# Final.net
KiCad netlist of a schematic drawn in EAGLE
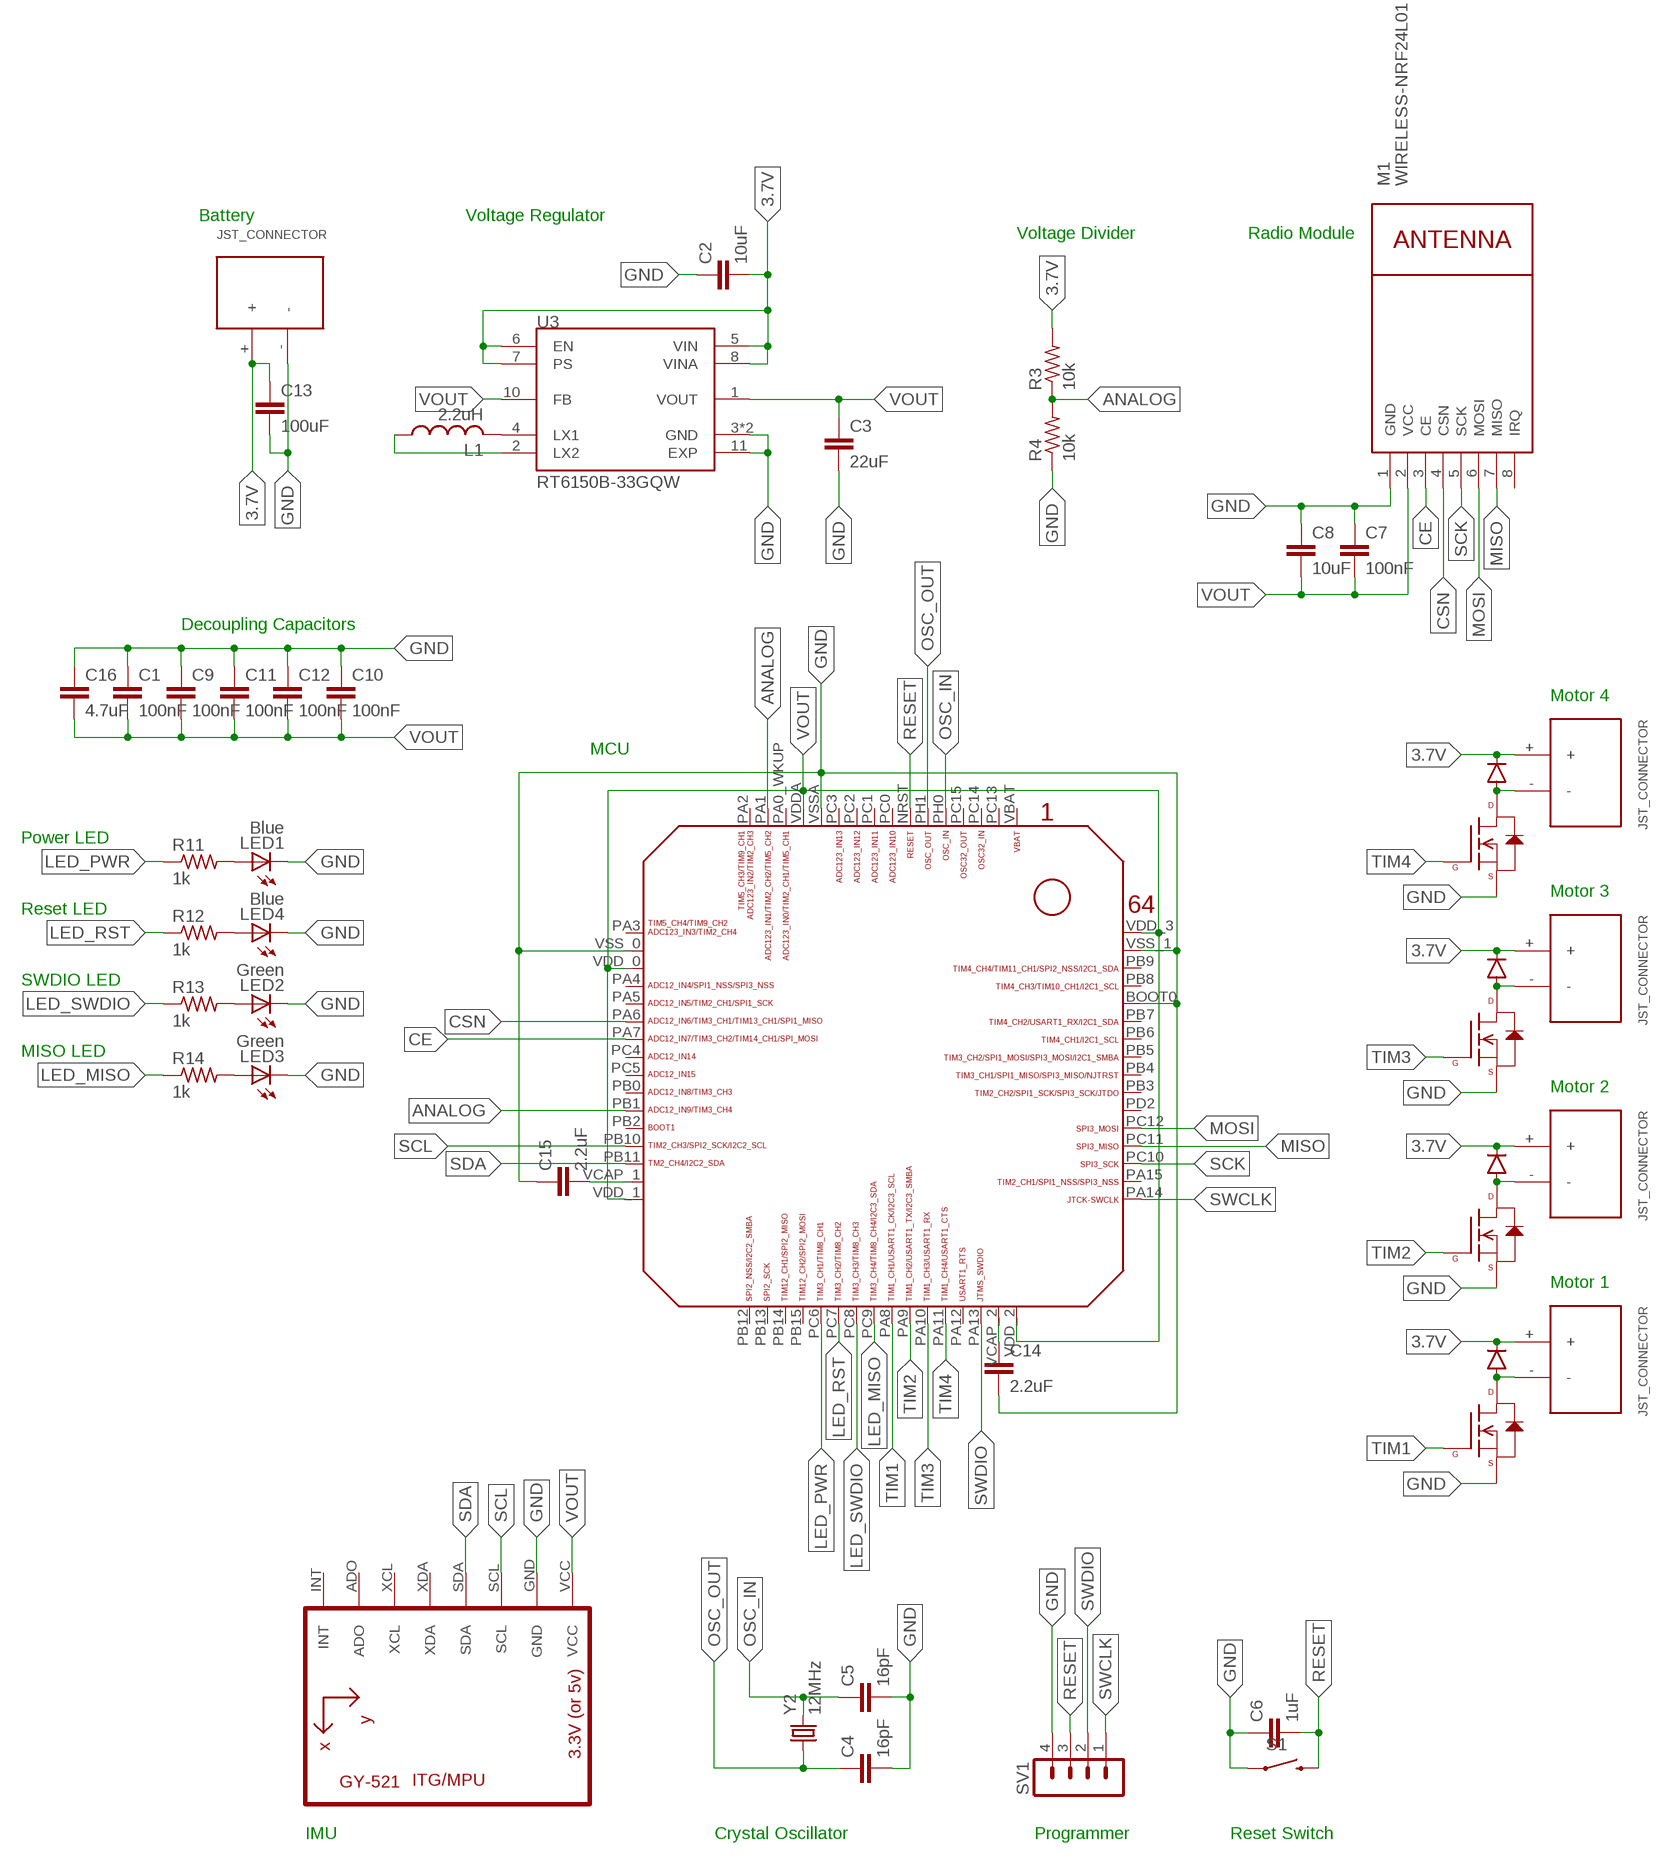
[diagram p0: schematic, sheet 1]

(export (version "E")
  (design (tool "Eeschema 10.0.6"))
  (components
    (comp (ref "C1")
      (value "100nF")
      (footprint "eagle-import:C0603")
      (libsource (lib "eagle-import") (part "rcl_334_C-EUC0603"))
    )
    (comp (ref "C2")
      (value "10uF")
      (footprint "eagle-import:C0603")
      (libsource (lib "eagle-import") (part "rcl_334_C-EUC0603"))
    )
    (comp (ref "C3")
      (value "22uF")
      (footprint "eagle-import:C0603")
      (libsource (lib "eagle-import") (part "rcl_334_C-EUC0603"))
    )
    (comp (ref "C4")
      (value "16pF")
      (footprint "eagle-import:C0603")
      (libsource (lib "eagle-import") (part "rcl_334_C-EUC0603"))
    )
    (comp (ref "C5")
      (value "16pF")
      (footprint "eagle-import:C0603")
      (libsource (lib "eagle-import") (part "rcl_334_C-EUC0603"))
    )
    (comp (ref "C6")
      (value "1uF")
      (footprint "eagle-import:C0603")
      (libsource (lib "eagle-import") (part "rcl_334_C-EUC0603"))
    )
    (comp (ref "C7")
      (value "100nF")
      (footprint "eagle-import:C0603")
      (libsource (lib "eagle-import") (part "rcl_334_C-EUC0603"))
    )
    (comp (ref "C8")
      (value "10uF")
      (footprint "eagle-import:C0603")
      (libsource (lib "eagle-import") (part "rcl_334_C-EUC0603"))
    )
    (comp (ref "C9")
      (value "100nF")
      (footprint "eagle-import:C0603")
      (libsource (lib "eagle-import") (part "rcl_334_C-EUC0603"))
    )
    (comp (ref "C10")
      (value "100nF")
      (footprint "eagle-import:C0603")
      (libsource (lib "eagle-import") (part "rcl_334_C-EUC0603"))
    )
    (comp (ref "C11")
      (value "100nF")
      (footprint "eagle-import:C0603")
      (libsource (lib "eagle-import") (part "rcl_334_C-EUC0603"))
    )
    (comp (ref "C12")
      (value "100nF")
      (footprint "eagle-import:C0603")
      (libsource (lib "eagle-import") (part "rcl_334_C-EUC0603"))
    )
    (comp (ref "C13")
      (value "100uF")
      (footprint "eagle-import:C1206")
      (libsource (lib "eagle-import") (part "rcl_334_C-EUC1206"))
    )
    (comp (ref "C14")
      (value "2.2uF")
      (footprint "eagle-import:C0603")
      (libsource (lib "eagle-import") (part "C-EUC0603"))
    )
    (comp (ref "C15")
      (value "2.2uF")
      (footprint "eagle-import:C0603")
      (libsource (lib "eagle-import") (part "C-EUC0603"))
    )
    (comp (ref "C16")
      (value "4.7uF")
      (footprint "eagle-import:C0603")
      (libsource (lib "eagle-import") (part "rcl_334_C-EUC0603"))
    )
    (comp (ref "L1")
      (value "2.2uH")
      (footprint "eagle-import:L0603")
      (libsource (lib "eagle-import") (part "L-USL0603"))
    )
    (comp (ref "LED1")
      (value "Blue")
      (footprint "eagle-import:CHIP-LED0603")
      (libsource (lib "eagle-import") (part "LEDCHIP-LED0603"))
    )
    (comp (ref "LED2")
      (value "Green")
      (footprint "eagle-import:CHIP-LED0603")
      (libsource (lib "eagle-import") (part "LEDCHIP-LED0603"))
    )
    (comp (ref "LED3")
      (value "Green")
      (footprint "eagle-import:CHIP-LED0603")
      (libsource (lib "eagle-import") (part "LEDCHIP-LED0603"))
    )
    (comp (ref "LED4")
      (value "Blue")
      (footprint "eagle-import:CHIP-LED0603")
      (libsource (lib "eagle-import") (part "LEDCHIP-LED0603"))
    )
    (comp (ref "M1")
      (value "WIRELESS-NRF24L01")
      (footprint "eagle-import:WIRELESS-NRF24L01")
      (libsource (lib "eagle-import") (part "WIRELESS-NRF24L01"))
    )
    (comp (ref "R3")
      (value "10k")
      (footprint "eagle-import:R0603")
      (libsource (lib "eagle-import") (part "R-US_R0603"))
    )
    (comp (ref "R4")
      (value "10k")
      (footprint "eagle-import:R0603")
      (libsource (lib "eagle-import") (part "R-US_R0603"))
    )
    (comp (ref "R11")
      (value "1k")
      (footprint "eagle-import:R0603")
      (libsource (lib "eagle-import") (part "R-US_R0603"))
    )
    (comp (ref "R12")
      (value "1k")
      (footprint "eagle-import:R0603")
      (libsource (lib "eagle-import") (part "R-US_R0603"))
    )
    (comp (ref "R13")
      (value "1k")
      (footprint "eagle-import:R0603")
      (libsource (lib "eagle-import") (part "R-US_R0603"))
    )
    (comp (ref "R14")
      (value "1k")
      (footprint "eagle-import:R0603")
      (libsource (lib "eagle-import") (part "R-US_R0603"))
    )
    (comp (ref "S1")
      (value "SWITCH-MOMENTARY-2SMD")
      (footprint "eagle-import:TACTILE-SWITCH-SMD")
      (libsource (lib "eagle-import") (part "SWITCH-MOMENTARY-2SMD"))
    )
    (comp (ref "SV1")
      (value "MA04-1")
      (footprint "eagle-import:MA04-1")
      (libsource (lib "eagle-import") (part "MA04-1"))
    )
    (comp (ref "U$1")
      (value "STM32F405/415_LQFP64")
      (footprint "eagle-import:STM32F405_415_LQFP64")
      (libsource (lib "eagle-import") (part "STM32F405/415_LQFP64"))
    )
    (comp (ref "U$2")
      (value "JST_CONNECTOR_FEMALE")
      (footprint "eagle-import:JST_CONNECTOR_FEMALE")
      (libsource (lib "eagle-import") (part "JST_CONNECTOR_FEMALE"))
    )
    (comp (ref "U$3")
      (value "JST_CONNECTOR_FEMALE")
      (footprint "eagle-import:JST_CONNECTOR_FEMALE")
      (libsource (lib "eagle-import") (part "JST_CONNECTOR_FEMALE"))
    )
    (comp (ref "U$4")
      (value "JST_CONNECTOR_FEMALE")
      (footprint "eagle-import:JST_CONNECTOR_FEMALE")
      (libsource (lib "eagle-import") (part "JST_CONNECTOR_FEMALE"))
    )
    (comp (ref "U$5")
      (value "JST_CONNECTOR_FEMALE")
      (footprint "eagle-import:JST_CONNECTOR_FEMALE")
      (libsource (lib "eagle-import") (part "JST_CONNECTOR_FEMALE"))
    )
    (comp (ref "U$6")
      (value "JST_CONNECTOR_FEMALE")
      (footprint "eagle-import:JST_CONNECTOR_FEMALE")
      (libsource (lib "eagle-import") (part "JST_CONNECTOR_FEMALE"))
    )
    (comp (ref "U$7")
      (value "N-CHANNEL-MOSFET-IRLML6244TRPBF")
      (footprint "eagle-import:SOT23-3")
      (libsource (lib "eagle-import") (part "N-CHANNEL-MOSFET-IRLML6244TRPBF"))
    )
    (comp (ref "U$8")
      (value "N-CHANNEL-MOSFET-IRLML6244TRPBF")
      (footprint "eagle-import:SOT23-3")
      (libsource (lib "eagle-import") (part "N-CHANNEL-MOSFET-IRLML6244TRPBF"))
    )
    (comp (ref "U$9")
      (value "N-CHANNEL-MOSFET-IRLML6244TRPBF")
      (footprint "eagle-import:SOT23-3")
      (libsource (lib "eagle-import") (part "N-CHANNEL-MOSFET-IRLML6244TRPBF"))
    )
    (comp (ref "U$10")
      (value "N-CHANNEL-MOSFET-IRLML6244TRPBF")
      (footprint "eagle-import:SOT23-3")
      (libsource (lib "eagle-import") (part "N-CHANNEL-MOSFET-IRLML6244TRPBF"))
    )
    (comp (ref "U$11")
      (value "DB2W40300L")
      (footprint "eagle-import:MINI2-F3-B")
      (libsource (lib "eagle-import") (part "DB2W40300L"))
    )
    (comp (ref "U$12")
      (value "DB2W40300L")
      (footprint "eagle-import:MINI2-F3-B")
      (libsource (lib "eagle-import") (part "DB2W40300L"))
    )
    (comp (ref "U$13")
      (value "DB2W40300L")
      (footprint "eagle-import:MINI2-F3-B")
      (libsource (lib "eagle-import") (part "DB2W40300L"))
    )
    (comp (ref "U$14")
      (value "DB2W40300L")
      (footprint "eagle-import:MINI2-F3-B")
      (libsource (lib "eagle-import") (part "DB2W40300L"))
    )
    (comp (ref "U2")
      (value "GY-521MPU6050")
      (footprint "eagle-import:GY-521")
      (libsource (lib "eagle-import") (part "GY-521MPU6050"))
    )
    (comp (ref "U3")
      (value "RT6150B-33GQW")
      (footprint "eagle-import:SON50P250X250X80-11N")
      (fields (field (name "DIGI-KEY_PART_NUMBER") "RT6150B-33GQWCT-ND") (field (name "MF") "Richtek USA"))
      (libsource (lib "eagle-import") (part "RT6150B-33GQW"))
    )
    (comp (ref "Y2")
      (value "12MHz")
      (footprint "eagle-import:HC49UP")
      (libsource (lib "eagle-import") (part "CRYSTALSMD"))
    )
  )
  (nets
    (net (code "1") (name "3.7V") (class "Default")
      (node (ref "C13") (pin "1") (pinfunction "1_1") (pintype "passive"))
      (node (ref "C2") (pin "2") (pinfunction "2_2") (pintype "passive"))
      (node (ref "R3") (pin "2") (pinfunction "2_2") (pintype "passive"))
      (node (ref "U$11") (pin "NEG") (pinfunction "GPIN_NEG") (pintype "passive"))
      (node (ref "U$12") (pin "NEG") (pinfunction "GPIN_NEG") (pintype "passive"))
      (node (ref "U$13") (pin "NEG") (pinfunction "GPIN_NEG") (pintype "passive"))
      (node (ref "U$14") (pin "NEG") (pinfunction "GPIN_NEG") (pintype "passive"))
      (node (ref "U$2") (pin "+") (pinfunction "+_+") (pintype "bidirectional"))
      (node (ref "U$3") (pin "+") (pinfunction "+_+") (pintype "bidirectional"))
      (node (ref "U$4") (pin "+") (pinfunction "+_+") (pintype "bidirectional"))
      (node (ref "U$5") (pin "+") (pinfunction "+_+") (pintype "bidirectional"))
      (node (ref "U$6") (pin "+") (pinfunction "+_+") (pintype "bidirectional"))
      (node (ref "U3") (pin "5") (pinfunction "VIN_5") (pintype "power_in"))
      (node (ref "U3") (pin "6") (pinfunction "EN_6") (pintype "input"))
      (node (ref "U3") (pin "7") (pinfunction "PS_7") (pintype "input"))
      (node (ref "U3") (pin "8") (pinfunction "VINA_8") (pintype "power_in"))
    )
    (net (code "2") (name "ANALOG") (class "Default")
      (node (ref "R3") (pin "1") (pinfunction "1_1") (pintype "passive"))
      (node (ref "R4") (pin "2") (pinfunction "2_2") (pintype "passive"))
      (node (ref "U$1") (pin "PA1") (pinfunction "PA1_PA1") (pintype "bidirectional"))
      (node (ref "U$1") (pin "PB1") (pinfunction "PB1_PB1") (pintype "bidirectional"))
    )
    (net (code "3") (name "CE") (class "Default")
      (node (ref "M1") (pin "3") (pinfunction "CE_3") (pintype "bidirectional"))
      (node (ref "U$1") (pin "PA7") (pinfunction "PA7_PA7") (pintype "bidirectional"))
    )
    (net (code "4") (name "CSN") (class "Default")
      (node (ref "M1") (pin "4") (pinfunction "CSN_4") (pintype "bidirectional"))
      (node (ref "U$1") (pin "PA6") (pinfunction "PA6_PA6") (pintype "bidirectional"))
    )
    (net (code "5") (name "GND") (class "Default")
      (node (ref "C1") (pin "1") (pinfunction "1_1") (pintype "passive"))
      (node (ref "C10") (pin "1") (pinfunction "1_1") (pintype "passive"))
      (node (ref "C11") (pin "1") (pinfunction "1_1") (pintype "passive"))
      (node (ref "C12") (pin "1") (pinfunction "1_1") (pintype "passive"))
      (node (ref "C13") (pin "2") (pinfunction "2_2") (pintype "passive"))
      (node (ref "C14") (pin "2") (pinfunction "2_2") (pintype "passive"))
      (node (ref "C15") (pin "1") (pinfunction "1_1") (pintype "passive"))
      (node (ref "C16") (pin "1") (pinfunction "1_1") (pintype "passive"))
      (node (ref "C2") (pin "1") (pinfunction "1_1") (pintype "passive"))
      (node (ref "C3") (pin "2") (pinfunction "2_2") (pintype "passive"))
      (node (ref "C4") (pin "2") (pinfunction "2_2") (pintype "passive"))
      (node (ref "C5") (pin "2") (pinfunction "2_2") (pintype "passive"))
      (node (ref "C6") (pin "1") (pinfunction "1_1") (pintype "passive"))
      (node (ref "C7") (pin "1") (pinfunction "1_1") (pintype "passive"))
      (node (ref "C8") (pin "1") (pinfunction "1_1") (pintype "passive"))
      (node (ref "C9") (pin "1") (pinfunction "1_1") (pintype "passive"))
      (node (ref "LED1") (pin "C") (pinfunction "C_C") (pintype "passive"))
      (node (ref "LED2") (pin "C") (pinfunction "C_C") (pintype "passive"))
      (node (ref "LED3") (pin "C") (pinfunction "C_C") (pintype "passive"))
      (node (ref "LED4") (pin "C") (pinfunction "C_C") (pintype "passive"))
      (node (ref "M1") (pin "1") (pinfunction "GND_1") (pintype "power_in"))
      (node (ref "R4") (pin "1") (pinfunction "1_1") (pintype "passive"))
      (node (ref "S1") (pin "1") (pinfunction "1_1") (pintype "passive"))
      (node (ref "SV1") (pin "4") (pinfunction "4_4") (pintype "passive"))
      (node (ref "U$1") (pin "BOOT0") (pinfunction "BOOT0_BOOT0") (pintype "bidirectional"))
      (node (ref "U$1") (pin "VSSA") (pinfunction "VSSA_VSSA") (pintype "bidirectional"))
      (node (ref "U$1") (pin "VSS_0") (pinfunction "VSS_0_VSS_0") (pintype "bidirectional"))
      (node (ref "U$1") (pin "VSS_1") (pinfunction "VSS_1_VSS_1") (pintype "bidirectional"))
      (node (ref "U$10") (pin "2") (pinfunction "S_2") (pintype "passive"))
      (node (ref "U$2") (pin "-") (pinfunction "-_-") (pintype "bidirectional"))
      (node (ref "U$7") (pin "2") (pinfunction "S_2") (pintype "passive"))
      (node (ref "U$8") (pin "2") (pinfunction "S_2") (pintype "passive"))
      (node (ref "U$9") (pin "2") (pinfunction "S_2") (pintype "passive"))
      (node (ref "U2") (pin "GND") (pinfunction "GND_GND") (pintype "bidirectional"))
      (node (ref "U3") (pin "11") (pinfunction "EXP_11") (pintype "passive"))
      (node (ref "U3") (pin "3") (pinfunction "GND_3") (pintype "power_in"))
      (node (ref "U3") (pin "9") (pinfunction "GND_9") (pintype "power_in"))
    )
    (net (code "6") (name "LED_MISO") (class "Default")
      (node (ref "R14") (pin "1") (pinfunction "1_1") (pintype "passive"))
      (node (ref "U$1") (pin "PC9") (pinfunction "PC9_PC9") (pintype "bidirectional"))
    )
    (net (code "7") (name "LED_PWR") (class "Default")
      (node (ref "R11") (pin "1") (pinfunction "1_1") (pintype "passive"))
      (node (ref "U$1") (pin "PC6") (pinfunction "PC6_PC6") (pintype "bidirectional"))
    )
    (net (code "8") (name "LED_RST") (class "Default")
      (node (ref "R12") (pin "1") (pinfunction "1_1") (pintype "passive"))
      (node (ref "U$1") (pin "PC7") (pinfunction "PC7_PC7") (pintype "bidirectional"))
    )
    (net (code "9") (name "LED_SWDIO") (class "Default")
      (node (ref "R13") (pin "1") (pinfunction "1_1") (pintype "passive"))
      (node (ref "U$1") (pin "PC8") (pinfunction "PC8_PC8") (pintype "bidirectional"))
    )
    (net (code "10") (name "MISO") (class "Default")
      (node (ref "M1") (pin "7") (pinfunction "MISO_7") (pintype "bidirectional"))
      (node (ref "U$1") (pin "PC11") (pinfunction "PC11_PC11") (pintype "bidirectional"))
    )
    (net (code "11") (name "MOSI") (class "Default")
      (node (ref "M1") (pin "6") (pinfunction "MOSI_6") (pintype "bidirectional"))
      (node (ref "U$1") (pin "PC12") (pinfunction "PC12_PC12") (pintype "bidirectional"))
    )
    (net (code "12") (name "Net-(C14-Pad1)") (class "Default")
      (node (ref "C14") (pin "1") (pinfunction "1_1") (pintype "passive"))
      (node (ref "U$1") (pin "VCAP_2") (pinfunction "VCAP_2_VCAP_2") (pintype "bidirectional"))
    )
    (net (code "13") (name "Net-(C15-Pad2)") (class "Default")
      (node (ref "C15") (pin "2") (pinfunction "2_2") (pintype "passive"))
      (node (ref "U$1") (pin "VCAP_1") (pinfunction "VCAP_1_VCAP_1") (pintype "bidirectional"))
    )
    (net (code "14") (name "Net-(LED1-PadA)") (class "Default")
      (node (ref "LED1") (pin "A") (pinfunction "A_A") (pintype "passive"))
      (node (ref "R11") (pin "2") (pinfunction "2_2") (pintype "passive"))
    )
    (net (code "15") (name "Net-(LED2-PadA)") (class "Default")
      (node (ref "LED2") (pin "A") (pinfunction "A_A") (pintype "passive"))
      (node (ref "R13") (pin "2") (pinfunction "2_2") (pintype "passive"))
    )
    (net (code "16") (name "Net-(LED3-PadA)") (class "Default")
      (node (ref "LED3") (pin "A") (pinfunction "A_A") (pintype "passive"))
      (node (ref "R14") (pin "2") (pinfunction "2_2") (pintype "passive"))
    )
    (net (code "17") (name "Net-(LED4-PadA)") (class "Default")
      (node (ref "LED4") (pin "A") (pinfunction "A_A") (pintype "passive"))
      (node (ref "R12") (pin "2") (pinfunction "2_2") (pintype "passive"))
    )
    (net (code "18") (name "Net-(U$10-D)") (class "Default")
      (node (ref "U$10") (pin "3") (pinfunction "D_3") (pintype "passive"))
      (node (ref "U$14") (pin "POS") (pinfunction "PPIN_POS") (pintype "passive"))
      (node (ref "U$6") (pin "-") (pinfunction "-_-") (pintype "bidirectional"))
    )
    (net (code "19") (name "Net-(U$11-PPIN)") (class "Default")
      (node (ref "U$11") (pin "POS") (pinfunction "PPIN_POS") (pintype "passive"))
      (node (ref "U$3") (pin "-") (pinfunction "-_-") (pintype "bidirectional"))
      (node (ref "U$9") (pin "3") (pinfunction "D_3") (pintype "passive"))
    )
    (net (code "20") (name "Net-(U$12-PPIN)") (class "Default")
      (node (ref "U$12") (pin "POS") (pinfunction "PPIN_POS") (pintype "passive"))
      (node (ref "U$5") (pin "-") (pinfunction "-_-") (pintype "bidirectional"))
      (node (ref "U$8") (pin "3") (pinfunction "D_3") (pintype "passive"))
    )
    (net (code "21") (name "Net-(U$13-PPIN)") (class "Default")
      (node (ref "U$13") (pin "POS") (pinfunction "PPIN_POS") (pintype "passive"))
      (node (ref "U$4") (pin "-") (pinfunction "-_-") (pintype "bidirectional"))
      (node (ref "U$7") (pin "3") (pinfunction "D_3") (pintype "passive"))
    )
    (net (code "22") (name "Net-(U3-LX1)") (class "Default")
      (node (ref "L1") (pin "2") (pinfunction "2_2") (pintype "passive"))
      (node (ref "U3") (pin "4") (pinfunction "LX1_4") (pintype "passive"))
    )
    (net (code "23") (name "Net-(U3-LX2)") (class "Default")
      (node (ref "L1") (pin "1") (pinfunction "1_1") (pintype "passive"))
      (node (ref "U3") (pin "2") (pinfunction "LX2_2") (pintype "passive"))
    )
    (net (code "24") (name "OSC_IN") (class "Default")
      (node (ref "C5") (pin "1") (pinfunction "1_1") (pintype "passive"))
      (node (ref "U$1") (pin "PH0") (pinfunction "PH0_PH0") (pintype "bidirectional"))
      (node (ref "Y2") (pin "2") (pinfunction "2_2") (pintype "passive"))
    )
    (net (code "25") (name "OSC_OUT") (class "Default")
      (node (ref "C4") (pin "1") (pinfunction "1_1") (pintype "passive"))
      (node (ref "U$1") (pin "PH1") (pinfunction "PH1_PH1") (pintype "bidirectional"))
      (node (ref "Y2") (pin "1") (pinfunction "1_1") (pintype "passive"))
    )
    (net (code "26") (name "RESET") (class "Default")
      (node (ref "C6") (pin "2") (pinfunction "2_2") (pintype "passive"))
      (node (ref "S1") (pin "3") (pinfunction "2_3") (pintype "passive"))
      (node (ref "SV1") (pin "3") (pinfunction "3_3") (pintype "passive"))
      (node (ref "U$1") (pin "NRST") (pinfunction "NRST_NRST") (pintype "bidirectional"))
    )
    (net (code "27") (name "SCK") (class "Default")
      (node (ref "M1") (pin "5") (pinfunction "SCK_5") (pintype "bidirectional"))
      (node (ref "U$1") (pin "PC10") (pinfunction "PC10_PC10") (pintype "bidirectional"))
    )
    (net (code "28") (name "SCL") (class "Default")
      (node (ref "U$1") (pin "PB10") (pinfunction "PB10_PB10") (pintype "bidirectional"))
      (node (ref "U2") (pin "SCL") (pinfunction "SCL_SCL") (pintype "bidirectional"))
    )
    (net (code "29") (name "SDA") (class "Default")
      (node (ref "U$1") (pin "PB11") (pinfunction "PB11_PB11") (pintype "bidirectional"))
      (node (ref "U2") (pin "SDA") (pinfunction "SDA_SDA") (pintype "bidirectional"))
    )
    (net (code "30") (name "SWCLK") (class "Default")
      (node (ref "SV1") (pin "1") (pinfunction "1_1") (pintype "passive"))
      (node (ref "U$1") (pin "PA14") (pinfunction "PA14_PA14") (pintype "bidirectional"))
    )
    (net (code "31") (name "SWDIO") (class "Default")
      (node (ref "SV1") (pin "2") (pinfunction "2_2") (pintype "passive"))
      (node (ref "U$1") (pin "PA13") (pinfunction "PA13_PA13") (pintype "bidirectional"))
    )
    (net (code "32") (name "TIM1") (class "Default")
      (node (ref "U$1") (pin "PA8") (pinfunction "PA8_PA8") (pintype "bidirectional"))
      (node (ref "U$10") (pin "1") (pinfunction "G_1") (pintype "passive"))
    )
    (net (code "33") (name "TIM2") (class "Default")
      (node (ref "U$1") (pin "PA9") (pinfunction "PA9_PA9") (pintype "bidirectional"))
      (node (ref "U$8") (pin "1") (pinfunction "G_1") (pintype "passive"))
    )
    (net (code "34") (name "TIM3") (class "Default")
      (node (ref "U$1") (pin "PA10") (pinfunction "PA10_PA10") (pintype "bidirectional"))
      (node (ref "U$7") (pin "1") (pinfunction "G_1") (pintype "passive"))
    )
    (net (code "35") (name "TIM4") (class "Default")
      (node (ref "U$1") (pin "PA11") (pinfunction "PA11_PA11") (pintype "bidirectional"))
      (node (ref "U$9") (pin "1") (pinfunction "G_1") (pintype "passive"))
    )
    (net (code "36") (name "VOUT") (class "Default")
      (node (ref "C1") (pin "2") (pinfunction "2_2") (pintype "passive"))
      (node (ref "C10") (pin "2") (pinfunction "2_2") (pintype "passive"))
      (node (ref "C11") (pin "2") (pinfunction "2_2") (pintype "passive"))
      (node (ref "C12") (pin "2") (pinfunction "2_2") (pintype "passive"))
      (node (ref "C16") (pin "2") (pinfunction "2_2") (pintype "passive"))
      (node (ref "C3") (pin "1") (pinfunction "1_1") (pintype "passive"))
      (node (ref "C7") (pin "2") (pinfunction "2_2") (pintype "passive"))
      (node (ref "C8") (pin "2") (pinfunction "2_2") (pintype "passive"))
      (node (ref "C9") (pin "2") (pinfunction "2_2") (pintype "passive"))
      (node (ref "M1") (pin "2") (pinfunction "VCC_2") (pintype "power_in"))
      (node (ref "U$1") (pin "VDDA") (pinfunction "VDDA_VDDA") (pintype "bidirectional"))
      (node (ref "U$1") (pin "VDD_0") (pinfunction "VDD_0_VDD_0") (pintype "bidirectional"))
      (node (ref "U$1") (pin "VDD_1") (pinfunction "VDD_1_VDD_1") (pintype "bidirectional"))
      (node (ref "U$1") (pin "VDD_2") (pinfunction "VDD_2_VDD_2") (pintype "bidirectional"))
      (node (ref "U$1") (pin "VDD_3") (pinfunction "VDD_3_VDD_3") (pintype "bidirectional"))
      (node (ref "U2") (pin "VCC") (pinfunction "VCC_VCC") (pintype "bidirectional"))
      (node (ref "U3") (pin "1") (pinfunction "VOUT_1") (pintype "output"))
      (node (ref "U3") (pin "10") (pinfunction "FB_10") (pintype "input"))
    )
    (net (code "37") (name "unconnected-(M1-IRQ-Pad8)") (class "Default")
      (node (ref "M1") (pin "8") (pinfunction "IRQ_8") (pintype "bidirectional"))
    )
    (net (code "38") (name "unconnected-(U$1-PA0_AKUP-PadPA0_WKUP)") (class "Default")
      (node (ref "U$1") (pin "PA0_WKUP") (pinfunction "PA0_AKUP_PA0_WKUP") (pintype "bidirectional"))
    )
    (net (code "39") (name "unconnected-(U$1-PadPA2)") (class "Default")
      (node (ref "U$1") (pin "PA2") (pinfunction "PA2_PA2") (pintype "bidirectional"))
    )
    (net (code "40") (name "unconnected-(U$1-PadPA3)") (class "Default")
      (node (ref "U$1") (pin "PA3") (pinfunction "PA3_PA3") (pintype "bidirectional"))
    )
    (net (code "41") (name "unconnected-(U$1-PadPA4)") (class "Default")
      (node (ref "U$1") (pin "PA4") (pinfunction "PA4_PA4") (pintype "bidirectional"))
    )
    (net (code "42") (name "unconnected-(U$1-PadPA5)") (class "Default")
      (node (ref "U$1") (pin "PA5") (pinfunction "PA5_PA5") (pintype "bidirectional"))
    )
    (net (code "43") (name "unconnected-(U$1-PadPA12)") (class "Default")
      (node (ref "U$1") (pin "PA12") (pinfunction "PA12_PA12") (pintype "bidirectional"))
    )
    (net (code "44") (name "unconnected-(U$1-PadPA15)") (class "Default")
      (node (ref "U$1") (pin "PA15") (pinfunction "PA15_PA15") (pintype "bidirectional"))
    )
    (net (code "45") (name "unconnected-(U$1-PadPB0)") (class "Default")
      (node (ref "U$1") (pin "PB0") (pinfunction "PB0_PB0") (pintype "bidirectional"))
    )
    (net (code "46") (name "unconnected-(U$1-PadPB2)") (class "Default")
      (node (ref "U$1") (pin "PB2") (pinfunction "PB2_PB2") (pintype "bidirectional"))
    )
    (net (code "47") (name "unconnected-(U$1-PadPB3)") (class "Default")
      (node (ref "U$1") (pin "PB3") (pinfunction "PB3_PB3") (pintype "bidirectional"))
    )
    (net (code "48") (name "unconnected-(U$1-PadPB4)") (class "Default")
      (node (ref "U$1") (pin "PB4") (pinfunction "PB4_PB4") (pintype "bidirectional"))
    )
    (net (code "49") (name "unconnected-(U$1-PadPB5)") (class "Default")
      (node (ref "U$1") (pin "PB5") (pinfunction "PB5_PB5") (pintype "bidirectional"))
    )
    (net (code "50") (name "unconnected-(U$1-PadPB6)") (class "Default")
      (node (ref "U$1") (pin "PB6") (pinfunction "PB6_PB6") (pintype "bidirectional"))
    )
    (net (code "51") (name "unconnected-(U$1-PadPB7)") (class "Default")
      (node (ref "U$1") (pin "PB7") (pinfunction "PB7_PB7") (pintype "bidirectional"))
    )
    (net (code "52") (name "unconnected-(U$1-PadPB8)") (class "Default")
      (node (ref "U$1") (pin "PB8") (pinfunction "PB8_PB8") (pintype "bidirectional"))
    )
    (net (code "53") (name "unconnected-(U$1-PadPB9)") (class "Default")
      (node (ref "U$1") (pin "PB9") (pinfunction "PB9_PB9") (pintype "bidirectional"))
    )
    (net (code "54") (name "unconnected-(U$1-PadPB12)") (class "Default")
      (node (ref "U$1") (pin "PB12") (pinfunction "PB12_PB12") (pintype "bidirectional"))
    )
    (net (code "55") (name "unconnected-(U$1-PadPB13)") (class "Default")
      (node (ref "U$1") (pin "PB13") (pinfunction "PB13_PB13") (pintype "bidirectional"))
    )
    (net (code "56") (name "unconnected-(U$1-PadPB14)") (class "Default")
      (node (ref "U$1") (pin "PB14") (pinfunction "PB14_PB14") (pintype "bidirectional"))
    )
    (net (code "57") (name "unconnected-(U$1-PadPB15)") (class "Default")
      (node (ref "U$1") (pin "PB15") (pinfunction "PB15_PB15") (pintype "bidirectional"))
    )
    (net (code "58") (name "unconnected-(U$1-PadPC0)") (class "Default")
      (node (ref "U$1") (pin "PC0") (pinfunction "PC0_PC0") (pintype "bidirectional"))
    )
    (net (code "59") (name "unconnected-(U$1-PadPC1)") (class "Default")
      (node (ref "U$1") (pin "PC1") (pinfunction "PC1_PC1") (pintype "bidirectional"))
    )
    (net (code "60") (name "unconnected-(U$1-PadPC2)") (class "Default")
      (node (ref "U$1") (pin "PC2") (pinfunction "PC2_PC2") (pintype "bidirectional"))
    )
    (net (code "61") (name "unconnected-(U$1-PadPC3)") (class "Default")
      (node (ref "U$1") (pin "PC3") (pinfunction "PC3_PC3") (pintype "bidirectional"))
    )
    (net (code "62") (name "unconnected-(U$1-PadPC4)") (class "Default")
      (node (ref "U$1") (pin "PC4") (pinfunction "PC4_PC4") (pintype "bidirectional"))
    )
    (net (code "63") (name "unconnected-(U$1-PadPC5)") (class "Default")
      (node (ref "U$1") (pin "PC5") (pinfunction "PC5_PC5") (pintype "bidirectional"))
    )
    (net (code "64") (name "unconnected-(U$1-PadPC13)") (class "Default")
      (node (ref "U$1") (pin "PC13") (pinfunction "PC13_PC13") (pintype "bidirectional"))
    )
    (net (code "65") (name "unconnected-(U$1-PadPC14)") (class "Default")
      (node (ref "U$1") (pin "PC14") (pinfunction "PC14_PC14") (pintype "bidirectional"))
    )
    (net (code "66") (name "unconnected-(U$1-PadPC15)") (class "Default")
      (node (ref "U$1") (pin "PC15") (pinfunction "PC15_PC15") (pintype "bidirectional"))
    )
    (net (code "67") (name "unconnected-(U$1-PadPD2)") (class "Default")
      (node (ref "U$1") (pin "PD2") (pinfunction "PD2_PD2") (pintype "bidirectional"))
    )
    (net (code "68") (name "unconnected-(U$1-PadVBAT)") (class "Default")
      (node (ref "U$1") (pin "VBAT") (pinfunction "VBAT_VBAT") (pintype "bidirectional"))
    )
    (net (code "69") (name "unconnected-(U2-PadADO)") (class "Default")
      (node (ref "U2") (pin "ADO") (pinfunction "ADO_ADO") (pintype "bidirectional"))
    )
    (net (code "70") (name "unconnected-(U2-PadINT)") (class "Default")
      (node (ref "U2") (pin "INT") (pinfunction "INT_INT") (pintype "bidirectional"))
    )
    (net (code "71") (name "unconnected-(U2-PadXCL)") (class "Default")
      (node (ref "U2") (pin "XCL") (pinfunction "XCL_XCL") (pintype "bidirectional"))
    )
    (net (code "72") (name "unconnected-(U2-PadXDA)") (class "Default")
      (node (ref "U2") (pin "XDA") (pinfunction "XDA_XDA") (pintype "bidirectional"))
    )
  )
)
